# COPY_VestibularVR_H1-module_v1_0.net
KiCad netlist of a schematic drawn in EAGLE
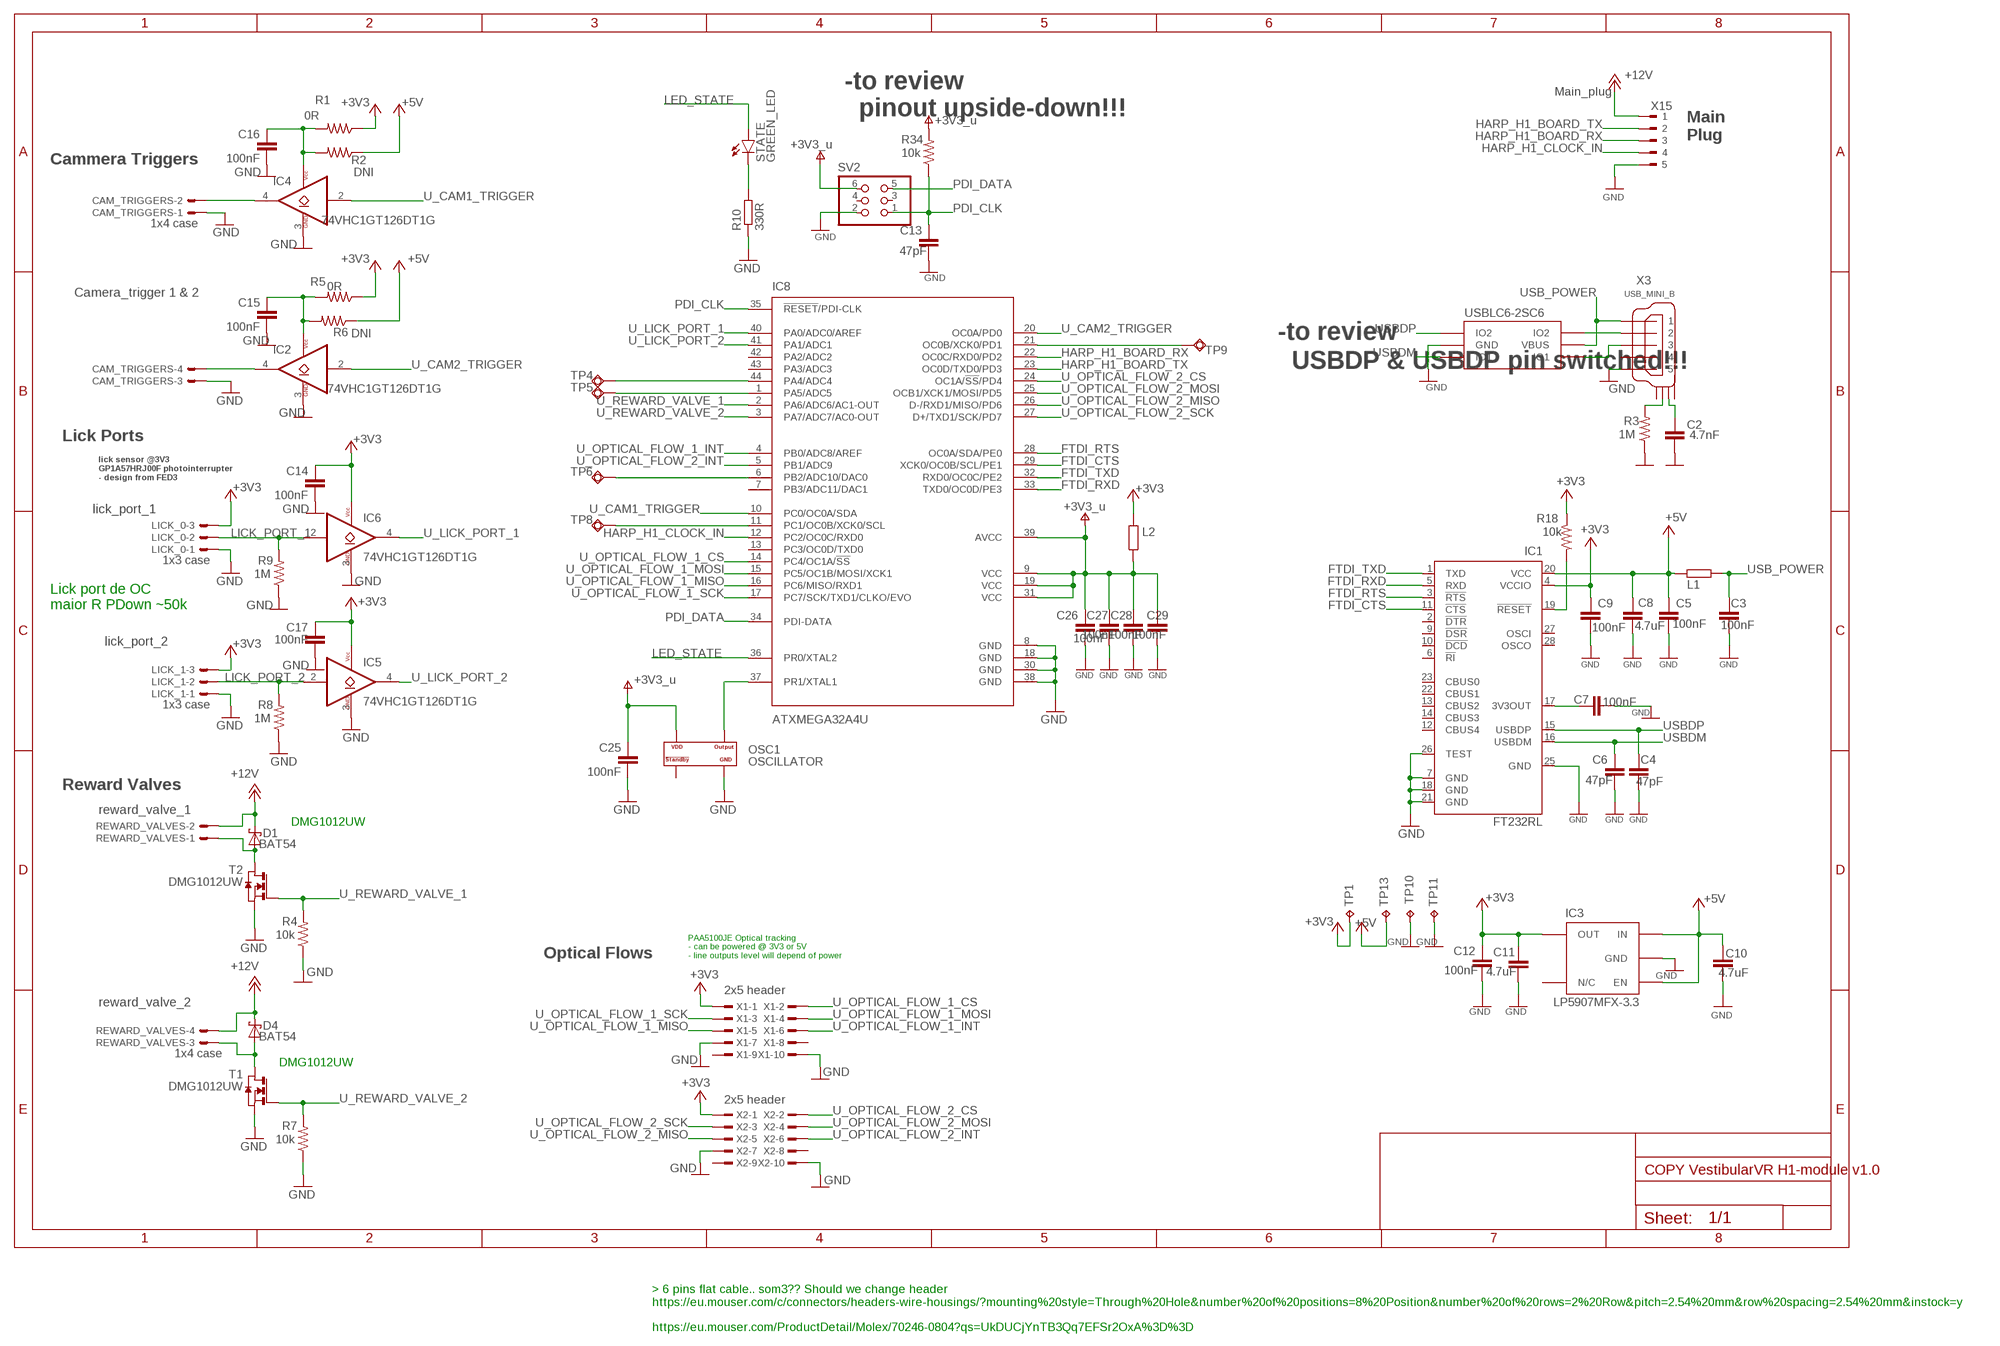
[diagram p0: schematic, sheet 1]

(export (version "E")
  (design (tool "Eeschema 10.0.6"))
  (components
    (comp (ref "C2")
      (value "4.7nF")
      (footprint "eagle-import:C0402K")
      (fields (field (name "MPN") "CC0402KRX7R8BB472"))
      (libsource (lib "eagle-import") (part "C-EUC0402K"))
    )
    (comp (ref "C3")
      (value "100nF")
      (footprint "eagle-import:C0402K")
      (fields (field (name "MPN") "C1005X7R1H104K050BB"))
      (libsource (lib "eagle-import") (part "C-EUC0402K"))
    )
    (comp (ref "C4")
      (value "47pF")
      (footprint "eagle-import:C0402K")
      (fields (field (name "MPN") "04025A470JAT2A"))
      (libsource (lib "eagle-import") (part "C-EUC0402K"))
    )
    (comp (ref "C5")
      (value "100nF")
      (footprint "eagle-import:C0402K")
      (fields (field (name "MPN") "C1005X7R1H104K050BB"))
      (libsource (lib "eagle-import") (part "C-EUC0402K"))
    )
    (comp (ref "C6")
      (value "47pF")
      (footprint "eagle-import:C0402K")
      (fields (field (name "MPN") "04025A470JAT2A"))
      (libsource (lib "eagle-import") (part "C-EUC0402K"))
    )
    (comp (ref "C7")
      (value "100nF")
      (footprint "eagle-import:C0402K")
      (fields (field (name "MPN") "C1005X7R1H104K050BB"))
      (libsource (lib "eagle-import") (part "C-EUC0402K"))
    )
    (comp (ref "C8")
      (value "4.7uF")
      (footprint "eagle-import:C0603")
      (fields (field (name "MPN") "C1608X6S1C475K080AC"))
      (libsource (lib "eagle-import") (part "C-EUC0603"))
    )
    (comp (ref "C9")
      (value "100nF")
      (footprint "eagle-import:C0402K")
      (fields (field (name "MPN") "C1005X7R1H104K050BB"))
      (libsource (lib "eagle-import") (part "C-EUC0402K"))
    )
    (comp (ref "C10")
      (value "4.7uF")
      (footprint "eagle-import:C0603K")
      (fields (field (name "MPN") "C1608X6S1C475K080AC"))
      (libsource (lib "eagle-import") (part "C-EUC0603K"))
    )
    (comp (ref "C11")
      (value "4.7uF")
      (footprint "eagle-import:C0603K")
      (fields (field (name "MPN") "C1608X6S1C475K080AC"))
      (libsource (lib "eagle-import") (part "C-EUC0603K"))
    )
    (comp (ref "C12")
      (value "100nF")
      (footprint "eagle-import:C0402K")
      (fields (field (name "MPN") "C1005X7R1H104K050BB"))
      (libsource (lib "eagle-import") (part "C-EUC0402K"))
    )
    (comp (ref "C13")
      (value "47pF")
      (footprint "eagle-import:C0402K")
      (fields (field (name "MPN") "04025A470JAT2A"))
      (libsource (lib "eagle-import") (part "C-EUC0402K"))
    )
    (comp (ref "C14")
      (value "100nF")
      (footprint "eagle-import:C0402K")
      (fields (field (name "MPN") "C1005X7R1H104K050BB"))
      (libsource (lib "eagle-import") (part "C-EUC0402K"))
    )
    (comp (ref "C15")
      (value "100nF")
      (footprint "eagle-import:C0402K")
      (fields (field (name "MPN") "C1005X7R1H104K050BB"))
      (libsource (lib "eagle-import") (part "C-EUC0402K"))
    )
    (comp (ref "C16")
      (value "100nF")
      (footprint "eagle-import:C0402K")
      (fields (field (name "MPN") "C1005X7R1H104K050BB"))
      (libsource (lib "eagle-import") (part "C-EUC0402K"))
    )
    (comp (ref "C17")
      (value "100nF")
      (footprint "eagle-import:C0402K")
      (fields (field (name "MPN") "C1005X7R1H104K050BB"))
      (libsource (lib "eagle-import") (part "C-EUC0402K"))
    )
    (comp (ref "C25")
      (value "100nF")
      (footprint "eagle-import:C0402K")
      (fields (field (name "MPN") "C1005X7R1H104K050BB"))
      (libsource (lib "eagle-import") (part "C-EUC0402K"))
    )
    (comp (ref "C26")
      (value "100nF")
      (footprint "eagle-import:C0402K")
      (fields (field (name "MPN") "C1005X7R1H104K050BB"))
      (libsource (lib "eagle-import") (part "C-EUC0402K"))
    )
    (comp (ref "C27")
      (value "100nF")
      (footprint "eagle-import:C0402K")
      (fields (field (name "MPN") "C1005X7R1H104K050BB"))
      (libsource (lib "eagle-import") (part "C-EUC0402K"))
    )
    (comp (ref "C28")
      (value "100nF")
      (footprint "eagle-import:C0402K")
      (fields (field (name "MPN") "C1005X7R1H104K050BB"))
      (libsource (lib "eagle-import") (part "C-EUC0402K"))
    )
    (comp (ref "C29")
      (value "100nF")
      (footprint "eagle-import:C0402K")
      (fields (field (name "MPN") "C1005X7R1H104K050BB"))
      (libsource (lib "eagle-import") (part "C-EUC0402K"))
    )
    (comp (ref "CAM_TRIGGERS")
      (value "1x4 case")
      (footprint "eagle-import:22-23-2041")
      (fields
        (field (name "MF") "MOLEX")
        (field (name "MPN") "22-23-2041")
        (field (name "MF_1") "-")
        (field (name "MPN_1") "282834-4")
        (field (name "OEPS") "OEPS070036")
      )
      (libsource (lib "eagle-import") (part "22-23-2041"))
    )
    (comp (ref "D1")
      (value "BAT54")
      (footprint "eagle-import:SOT23")
      (fields (field (name "MPN") "BAT54SLT1G"))
      (libsource (lib "eagle-import") (part "BAT54"))
    )
    (comp (ref "D4")
      (value "BAT54")
      (footprint "eagle-import:SOT23")
      (fields (field (name "MPN") "BAT54SLT1G"))
      (libsource (lib "eagle-import") (part "BAT54"))
    )
    (comp (ref "IC1")
      (value "FT232RL")
      (footprint "eagle-import:SSOP28")
      (libsource (lib "eagle-import") (part "FT232RL"))
    )
    (comp (ref "IC2")
      (value "74VHC1GT126DT1G")
      (footprint "eagle-import:SOT23-5")
      (fields (field (name "MPN") "M74VHC1GT126DT1G"))
      (libsource (lib "eagle-import") (part "74LVC1G07DBV"))
    )
    (comp (ref "IC3")
      (value "LP5907MFX-3.3")
      (footprint "eagle-import:TSOT23-5")
      (fields (field (name "MPN") "LP5907MFX-3.3/NOPB"))
      (libsource (lib "eagle-import") (part "TLV700XX"))
    )
    (comp (ref "IC4")
      (value "74VHC1GT126DT1G")
      (footprint "eagle-import:SOT23-5")
      (fields (field (name "MPN") "M74VHC1GT126DT1G"))
      (libsource (lib "eagle-import") (part "74LVC1G07DBV"))
    )
    (comp (ref "IC5")
      (value "74VHC1GT126DT1G")
      (footprint "eagle-import:SOT23-5")
      (fields (field (name "MPN") "M74VHC1GT126DT1G"))
      (libsource (lib "eagle-import") (part "74LVC1G07DBV"))
    )
    (comp (ref "IC6")
      (value "74VHC1GT126DT1G")
      (footprint "eagle-import:SOT23-5")
      (fields (field (name "MPN") "M74VHC1GT126DT1G"))
      (libsource (lib "eagle-import") (part "74LVC1G07DBV"))
    )
    (comp (ref "IC7")
      (value "USBLC6-2SC6")
      (footprint "eagle-import:SOT23-6L")
      (libsource (lib "eagle-import") (part "USBLC6-2SC6"))
    )
    (comp (ref "IC8")
      (value "ATXMEGA32A4U")
      (footprint "eagle-import:TQFP44")
      (fields (field (name "MPN") "ATXMEGA32A4U-AUR"))
      (libsource (lib "eagle-import") (part "XMEGA-A4_AT-XMEGA-XXA4-AUTQFP44"))
    )
    (comp (ref "L1")
      (value "40R@100MHz")
      (footprint "eagle-import:R0603")
      (fields (field (name "MPN") "MI0805K400R-10"))
      (libsource (lib "eagle-import") (part "R-EU_R0603"))
    )
    (comp (ref "L2")
      (value "40R@100MHz")
      (footprint "eagle-import:R0603")
      (fields (field (name "MPN") "MI0805K400R-10"))
      (libsource (lib "eagle-import") (part "R-EU_R0603"))
    )
    (comp (ref "LICK_0")
      (value "1x3 case")
      (footprint "eagle-import:22-23-2031")
      (fields
        (field (name "MF") "MOLEX")
        (field (name "MPN") "22-23-2031")
        (field (name "MF_1") "-")
        (field (name "MPN_1") "282834-3")
        (field (name "OEPS") "OEPS070035")
      )
      (libsource (lib "eagle-import") (part "22-23-2031"))
    )
    (comp (ref "LICK_1")
      (value "1x3 case")
      (footprint "eagle-import:22-23-2031")
      (fields
        (field (name "MF") "MOLEX")
        (field (name "MPN") "22-23-2031")
        (field (name "MF_1") "-")
        (field (name "MPN_1") "282834-3")
        (field (name "OEPS") "OEPS070035")
      )
      (libsource (lib "eagle-import") (part "22-23-2031"))
    )
    (comp (ref "OSC1")
      (value "OSCILLATOR")
      (footprint "eagle-import:OSCILLATOR_3.2X2.5")
      (fields (field (name "MPN") "DSC1001CI5-032.0000"))
      (libsource (lib "eagle-import") (part "OSCILLATOR"))
    )
    (comp (ref "R1")
      (value "0R")
      (footprint "eagle-import:R0402@1")
      (fields (field (name "MPN") "RC0402JR-070RL"))
      (libsource (lib "eagle-import") (part "R-US_R0402"))
    )
    (comp (ref "R2")
      (value "DNI")
      (footprint "eagle-import:R0402@1")
      (libsource (lib "eagle-import") (part "R-US_R0402"))
    )
    (comp (ref "R3")
      (value "1M")
      (footprint "eagle-import:R0402@1")
      (fields (field (name "MPN") "CRCW04021M00FKED"))
      (libsource (lib "eagle-import") (part "R-US_R0402"))
    )
    (comp (ref "R4")
      (value "10k")
      (footprint "eagle-import:R0402@1")
      (fields (field (name "MPN") "CRCW040210K0FKED"))
      (libsource (lib "eagle-import") (part "R-US_R0402"))
    )
    (comp (ref "R5")
      (value "0R")
      (footprint "eagle-import:R0402@1")
      (fields (field (name "MPN") "RC0402JR-070RL"))
      (libsource (lib "eagle-import") (part "R-US_R0402"))
    )
    (comp (ref "R6")
      (value "DNI")
      (footprint "eagle-import:R0402@1")
      (libsource (lib "eagle-import") (part "R-US_R0402"))
    )
    (comp (ref "R7")
      (value "10k")
      (footprint "eagle-import:R0402@1")
      (fields (field (name "MPN") "CRCW040210K0FKED"))
      (libsource (lib "eagle-import") (part "R-US_R0402"))
    )
    (comp (ref "R8")
      (value "1M")
      (footprint "eagle-import:R0402@1")
      (fields (field (name "MPN") "CRCW04021M00FKED"))
      (libsource (lib "eagle-import") (part "R-US_R0402"))
    )
    (comp (ref "R9")
      (value "1M")
      (footprint "eagle-import:R0402@1")
      (fields (field (name "MPN") "CRCW04021M00FKED"))
      (libsource (lib "eagle-import") (part "R-US_R0402"))
    )
    (comp (ref "R10")
      (value "330R")
      (footprint "eagle-import:R0402")
      (fields (field (name "MPN") "RC0402FR-07330RL"))
      (libsource (lib "eagle-import") (part "R-EU_R0402"))
    )
    (comp (ref "R18")
      (value "10k")
      (footprint "eagle-import:R0402@1")
      (fields (field (name "MPN") "CRCW040210K0FKED"))
      (libsource (lib "eagle-import") (part "R-US_R0402"))
    )
    (comp (ref "R34")
      (value "10k")
      (footprint "eagle-import:R0402@1")
      (fields (field (name "MPN") "CRCW040210K0FKED"))
      (libsource (lib "eagle-import") (part "R-US_R0402"))
    )
    (comp (ref "REWARD_VALVES")
      (value "1x4 case")
      (footprint "eagle-import:22-23-2041")
      (fields
        (field (name "MF") "MOLEX")
        (field (name "MPN") "22-23-2041")
        (field (name "MF_1") "-")
        (field (name "MPN_1") "282834-4")
        (field (name "OEPS") "OEPS070036")
      )
      (libsource (lib "eagle-import") (part "22-23-2041"))
    )
    (comp (ref "STATE")
      (value "GREEN_LED")
      (footprint "eagle-import:CHIP-LED0603")
      (fields (field (name "MPN") "LTST-C191KGKT"))
      (libsource (lib "eagle-import") (part "LEDCHIP-LED0603"))
    )
    (comp (ref "SV2")
      (value "PINHD-2X3")
      (footprint "eagle-import:2X03")
      (fields (field (name "MPN") "609-3210-ND"))
      (libsource (lib "eagle-import") (part "PINHD-2X3"))
    )
    (comp (ref "T1")
      (value "DMG1012UW")
      (footprint "eagle-import:SOT323")
      (fields (field (name "MPN") "DMG1012UW-7"))
      (libsource (lib "eagle-import") (part "DMG1012UW-7"))
    )
    (comp (ref "T2")
      (value "DMG1012UW")
      (footprint "eagle-import:SOT323")
      (fields (field (name "MPN") "DMG1012UW-7"))
      (libsource (lib "eagle-import") (part "DMG1012UW-7"))
    )
    (comp (ref "TP1")
      (value "NO_COMPONENT")
      (footprint "eagle-import:B1,27")
      (libsource (lib "eagle-import") (part "TPB1,27"))
    )
    (comp (ref "TP4")
      (value "NO_COMPONENT")
      (footprint "eagle-import:TP11R")
      (libsource (lib "eagle-import") (part "TPSQTP11R"))
    )
    (comp (ref "TP5")
      (value "NO_COMPONENT")
      (footprint "eagle-import:TP11R")
      (libsource (lib "eagle-import") (part "TPSQTP11R"))
    )
    (comp (ref "TP6")
      (value "NO_COMPONENT")
      (footprint "eagle-import:TP11R")
      (libsource (lib "eagle-import") (part "TPSQTP11R"))
    )
    (comp (ref "TP8")
      (value "NO_COMPONENT")
      (footprint "eagle-import:TP11R")
      (libsource (lib "eagle-import") (part "TPSQTP11R"))
    )
    (comp (ref "TP9")
      (value "NO_COMPONENT")
      (footprint "eagle-import:TP11R")
      (libsource (lib "eagle-import") (part "TPSQTP11R"))
    )
    (comp (ref "TP10")
      (value "NO_COMPONENT")
      (footprint "eagle-import:B1,27")
      (libsource (lib "eagle-import") (part "TPB1,27"))
    )
    (comp (ref "TP11")
      (value "NO_COMPONENT")
      (footprint "eagle-import:B1,27")
      (libsource (lib "eagle-import") (part "TPB1,27"))
    )
    (comp (ref "TP13")
      (value "NO_COMPONENT")
      (footprint "eagle-import:B1,27")
      (libsource (lib "eagle-import") (part "TPB1,27"))
    )
    (comp (ref "X1")
      (value "2x5 header")
      (footprint "eagle-import:TSW-105-02-S-D")
      (fields (field (name "MPN") "2x5 header") (field (name "OEPS") "n.a."))
      (libsource (lib "eagle-import") (part "TSW-105-02-S-D"))
    )
    (comp (ref "X2")
      (value "2x5 header")
      (footprint "eagle-import:TSW-105-02-S-D")
      (fields (field (name "MPN") "2x5 header") (field (name "OEPS") "n.a."))
      (libsource (lib "eagle-import") (part "TSW-105-02-S-D"))
    )
    (comp (ref "X3")
      (value "USB_MINI_B")
      (footprint "eagle-import:240-0002-1")
      (fields (field (name "MPN") "UX60-MB-5S8"))
      (libsource (lib "eagle-import") (part "USB_MINI_B"))
    )
    (comp (ref "X15")
      (value "Main_plug")
      (footprint "eagle-import:90G-5")
      (fields (field (name "MPN") "20.155MH/5-E"))
      (libsource (lib "eagle-import") (part "90G-5"))
    )
  )
  (nets
    (net (code "1") (name "+3V3") (class "Default")
      (node (ref "C11") (pin "1") (pinfunction "1_1") (pintype "passive"))
      (node (ref "C12") (pin "1") (pinfunction "1_1") (pintype "passive"))
      (node (ref "C14") (pin "1") (pinfunction "1_1") (pintype "passive"))
      (node (ref "C17") (pin "1") (pinfunction "1_1") (pintype "passive"))
      (node (ref "C9") (pin "1") (pinfunction "1_1") (pintype "passive"))
      (node (ref "IC1") (pin "4") (pinfunction "VCCIO_4") (pintype "power_in"))
      (node (ref "IC3") (pin "5") (pinfunction "OUT_5") (pintype "bidirectional"))
      (node (ref "IC5") (pin "5") (pinfunction "VCC_5") (pintype "bidirectional"))
      (node (ref "IC6") (pin "5") (pinfunction "VCC_5") (pintype "bidirectional"))
      (node (ref "L2") (pin "2") (pinfunction "2_2") (pintype "passive"))
      (node (ref "LICK_0") (pin "3") (pinfunction "S_3") (pintype "passive"))
      (node (ref "LICK_1") (pin "3") (pinfunction "S_3") (pintype "passive"))
      (node (ref "R1") (pin "1") (pinfunction "1_1") (pintype "passive"))
      (node (ref "R18") (pin "1") (pinfunction "1_1") (pintype "passive"))
      (node (ref "R5") (pin "1") (pinfunction "1_1") (pintype "passive"))
      (node (ref "TP1") (pin "TP") (pinfunction "TP_TP") (pintype "input"))
      (node (ref "X1") (pin "1") (pinfunction "1_1") (pintype "passive"))
      (node (ref "X2") (pin "1") (pinfunction "1_1") (pintype "passive"))
    )
    (net (code "2") (name "+3V3_u") (class "Default")
      (node (ref "C25") (pin "1") (pinfunction "1_1") (pintype "passive"))
      (node (ref "C26") (pin "1") (pinfunction "1_1") (pintype "passive"))
      (node (ref "C27") (pin "1") (pinfunction "1_1") (pintype "passive"))
      (node (ref "C28") (pin "1") (pinfunction "1_1") (pintype "passive"))
      (node (ref "C29") (pin "1") (pinfunction "1_1") (pintype "passive"))
      (node (ref "IC8") (pin "19") (pinfunction "VCC_19") (pintype "power_in"))
      (node (ref "IC8") (pin "31") (pinfunction "VCC_31") (pintype "power_in"))
      (node (ref "IC8") (pin "39") (pinfunction "AVCC_39") (pintype "power_in"))
      (node (ref "IC8") (pin "9") (pinfunction "VCC_9") (pintype "power_in"))
      (node (ref "L2") (pin "1") (pinfunction "1_1") (pintype "passive"))
      (node (ref "OSC1") (pin "P$4") (pinfunction "VDD_P$4") (pintype "passive"))
      (node (ref "R34") (pin "2") (pinfunction "2_2") (pintype "passive"))
      (node (ref "SV2") (pin "6") (pinfunction "6_6") (pintype "passive"))
    )
    (net (code "3") (name "+5V") (class "Default")
      (node (ref "C10") (pin "1") (pinfunction "1_1") (pintype "passive"))
      (node (ref "C5") (pin "1") (pinfunction "1_1") (pintype "passive"))
      (node (ref "C8") (pin "1") (pinfunction "1_1") (pintype "passive"))
      (node (ref "IC1") (pin "20") (pinfunction "VCC_20") (pintype "power_in"))
      (node (ref "IC3") (pin "1") (pinfunction "IN_1") (pintype "bidirectional"))
      (node (ref "IC3") (pin "3") (pinfunction "EN_3") (pintype "bidirectional"))
      (node (ref "L1") (pin "1") (pinfunction "1_1") (pintype "passive"))
      (node (ref "R2") (pin "1") (pinfunction "1_1") (pintype "passive"))
      (node (ref "R6") (pin "1") (pinfunction "1_1") (pintype "passive"))
      (node (ref "TP13") (pin "TP") (pinfunction "TP_TP") (pintype "input"))
    )
    (net (code "4") (name "+12V") (class "Default")
      (node (ref "D1") (pin "3") (pinfunction "C_3") (pintype "passive"))
      (node (ref "D4") (pin "3") (pinfunction "C_3") (pintype "passive"))
      (node (ref "REWARD_VALVES") (pin "2") (pinfunction "S_2") (pintype "passive"))
      (node (ref "REWARD_VALVES") (pin "4") (pinfunction "S_4") (pintype "passive"))
      (node (ref "X15") (pin "1") (pinfunction "1_1") (pintype "passive"))
    )
    (net (code "5") (name "/FTDI_CTS") (class "Default")
      (node (ref "IC1") (pin "11") (pinfunction "~{CTS}_11") (pintype "input"))
      (node (ref "IC8") (pin "29") (pinfunction "XCK0/OC0B/SCL/PE1_29") (pintype "bidirectional"))
    )
    (net (code "6") (name "/FTDI_RTS") (class "Default")
      (node (ref "IC1") (pin "3") (pinfunction "~{RTS}_3") (pintype "output"))
      (node (ref "IC8") (pin "28") (pinfunction "OC0A/SDA/PE0_28") (pintype "bidirectional"))
    )
    (net (code "7") (name "/FTDI_RXD") (class "Default")
      (node (ref "IC1") (pin "5") (pinfunction "RXD_5") (pintype "input"))
      (node (ref "IC8") (pin "33") (pinfunction "TXD0/OC0D/PE3_33") (pintype "bidirectional"))
    )
    (net (code "8") (name "/FTDI_TXD") (class "Default")
      (node (ref "IC1") (pin "1") (pinfunction "TXD_1") (pintype "output"))
      (node (ref "IC8") (pin "32") (pinfunction "RXD0/OC0C/PE2_32") (pintype "bidirectional"))
    )
    (net (code "9") (name "/HARP_H1_BOARD_RX") (class "Default")
      (node (ref "IC8") (pin "22") (pinfunction "OC0C/RXD0/PD2_22") (pintype "bidirectional"))
      (node (ref "X15") (pin "3") (pinfunction "3_3") (pintype "passive"))
    )
    (net (code "10") (name "/HARP_H1_BOARD_TX") (class "Default")
      (node (ref "IC8") (pin "23") (pinfunction "OC0D/TXD0/PD3_23") (pintype "bidirectional"))
      (node (ref "X15") (pin "2") (pinfunction "2_2") (pintype "passive"))
    )
    (net (code "11") (name "/HARP_H1_CLOCK_IN") (class "Default")
      (node (ref "IC8") (pin "12") (pinfunction "PC2/OC0C/RXD0_12") (pintype "bidirectional"))
      (node (ref "X15") (pin "4") (pinfunction "4_4") (pintype "passive"))
    )
    (net (code "12") (name "/LED_STATE") (class "Default")
      (node (ref "IC8") (pin "36") (pinfunction "PR0/XTAL2_36") (pintype "bidirectional"))
      (node (ref "STATE") (pin "A") (pinfunction "A_A") (pintype "passive"))
    )
    (net (code "13") (name "/LICK_PORT_1") (class "Default")
      (node (ref "IC6") (pin "2") (pinfunction "A_2") (pintype "bidirectional"))
      (node (ref "LICK_0") (pin "2") (pinfunction "S_2") (pintype "passive"))
      (node (ref "R9") (pin "2") (pinfunction "2_2") (pintype "passive"))
    )
    (net (code "14") (name "/LICK_PORT_2") (class "Default")
      (node (ref "IC5") (pin "2") (pinfunction "A_2") (pintype "bidirectional"))
      (node (ref "LICK_1") (pin "2") (pinfunction "S_2") (pintype "passive"))
      (node (ref "R8") (pin "2") (pinfunction "2_2") (pintype "passive"))
    )
    (net (code "15") (name "/PDI_CLK") (class "Default")
      (node (ref "C13") (pin "1") (pinfunction "1_1") (pintype "passive"))
      (node (ref "IC8") (pin "35") (pinfunction "~{RESET}/PDI-CLK_35") (pintype "input"))
      (node (ref "R34") (pin "1") (pinfunction "1_1") (pintype "passive"))
      (node (ref "SV2") (pin "1") (pinfunction "1_1") (pintype "passive"))
    )
    (net (code "16") (name "/PDI_DATA") (class "Default")
      (node (ref "IC8") (pin "34") (pinfunction "PDI-DATA_34") (pintype "bidirectional"))
      (node (ref "SV2") (pin "5") (pinfunction "5_5") (pintype "passive"))
    )
    (net (code "17") (name "/USBDM") (class "Default")
      (node (ref "C6") (pin "1") (pinfunction "1_1") (pintype "passive"))
      (node (ref "IC1") (pin "16") (pinfunction "USBDM_16") (pintype "bidirectional"))
      (node (ref "IC7") (pin "P$1") (pinfunction "IO1_P$1") (pintype "bidirectional"))
    )
    (net (code "18") (name "/USBDP") (class "Default")
      (node (ref "C4") (pin "1") (pinfunction "1_1") (pintype "passive"))
      (node (ref "IC1") (pin "15") (pinfunction "USBDP_15") (pintype "bidirectional"))
      (node (ref "IC7") (pin "P$3") (pinfunction "IO2_P$3") (pintype "bidirectional"))
    )
    (net (code "19") (name "/USB_POWER") (class "Default")
      (node (ref "C3") (pin "1") (pinfunction "1_1") (pintype "passive"))
      (node (ref "IC7") (pin "P$5") (pinfunction "VBUS_P$5") (pintype "bidirectional"))
      (node (ref "L1") (pin "2") (pinfunction "2_2") (pintype "passive"))
      (node (ref "X3") (pin "P$1") (pinfunction "1_P$1") (pintype "bidirectional"))
    )
    (net (code "20") (name "/U_CAM1_TRIGGER") (class "Default")
      (node (ref "IC4") (pin "2") (pinfunction "A_2") (pintype "bidirectional"))
      (node (ref "IC8") (pin "10") (pinfunction "PC0/OC0A/SDA_10") (pintype "bidirectional"))
    )
    (net (code "21") (name "/U_CAM2_TRIGGER") (class "Default")
      (node (ref "IC2") (pin "2") (pinfunction "A_2") (pintype "bidirectional"))
      (node (ref "IC8") (pin "20") (pinfunction "OC0A/PD0_20") (pintype "bidirectional"))
    )
    (net (code "22") (name "/U_LICK_PORT_1") (class "Default")
      (node (ref "IC6") (pin "4") (pinfunction "Y_4") (pintype "bidirectional"))
      (node (ref "IC8") (pin "40") (pinfunction "PA0/ADC0/AREF_40") (pintype "bidirectional"))
    )
    (net (code "23") (name "/U_LICK_PORT_2") (class "Default")
      (node (ref "IC5") (pin "4") (pinfunction "Y_4") (pintype "bidirectional"))
      (node (ref "IC8") (pin "41") (pinfunction "PA1/ADC1_41") (pintype "bidirectional"))
    )
    (net (code "24") (name "/U_OPTICAL_FLOW_1_CS") (class "Default")
      (node (ref "IC8") (pin "14") (pinfunction "PC4/OC1A/~{SS}_14") (pintype "bidirectional"))
      (node (ref "X1") (pin "2") (pinfunction "1_2") (pintype "passive"))
    )
    (net (code "25") (name "/U_OPTICAL_FLOW_1_INT") (class "Default")
      (node (ref "IC8") (pin "4") (pinfunction "PB0/ADC8/AREF_4") (pintype "bidirectional"))
      (node (ref "X1") (pin "6") (pinfunction "1_6") (pintype "passive"))
    )
    (net (code "26") (name "/U_OPTICAL_FLOW_1_MISO") (class "Default")
      (node (ref "IC8") (pin "16") (pinfunction "PC6/MISO/RXD1_16") (pintype "bidirectional"))
      (node (ref "X1") (pin "5") (pinfunction "1_5") (pintype "passive"))
    )
    (net (code "27") (name "/U_OPTICAL_FLOW_1_MOSI") (class "Default")
      (node (ref "IC8") (pin "15") (pinfunction "PC5/OC1B/MOSI/XCK1_15") (pintype "bidirectional"))
      (node (ref "X1") (pin "4") (pinfunction "1_4") (pintype "passive"))
    )
    (net (code "28") (name "/U_OPTICAL_FLOW_1_SCK") (class "Default")
      (node (ref "IC8") (pin "17") (pinfunction "PC7/SCK/TXD1/CLKO/EVO_17") (pintype "bidirectional"))
      (node (ref "X1") (pin "3") (pinfunction "1_3") (pintype "passive"))
    )
    (net (code "29") (name "/U_OPTICAL_FLOW_2_CS") (class "Default")
      (node (ref "IC8") (pin "24") (pinfunction "OC1A/~{SS}/PD4_24") (pintype "bidirectional"))
      (node (ref "X2") (pin "2") (pinfunction "1_2") (pintype "passive"))
    )
    (net (code "30") (name "/U_OPTICAL_FLOW_2_INT") (class "Default")
      (node (ref "IC8") (pin "5") (pinfunction "PB1/ADC9_5") (pintype "bidirectional"))
      (node (ref "X2") (pin "6") (pinfunction "1_6") (pintype "passive"))
    )
    (net (code "31") (name "/U_OPTICAL_FLOW_2_MISO") (class "Default")
      (node (ref "IC8") (pin "26") (pinfunction "D-/RXD1/MISO/PD6_26") (pintype "bidirectional"))
      (node (ref "X2") (pin "5") (pinfunction "1_5") (pintype "passive"))
    )
    (net (code "32") (name "/U_OPTICAL_FLOW_2_MOSI") (class "Default")
      (node (ref "IC8") (pin "25") (pinfunction "OCB1/XCK1/MOSI/PD5_25") (pintype "bidirectional"))
      (node (ref "X2") (pin "4") (pinfunction "1_4") (pintype "passive"))
    )
    (net (code "33") (name "/U_OPTICAL_FLOW_2_SCK") (class "Default")
      (node (ref "IC8") (pin "27") (pinfunction "D+/TXD1/SCK/PD7_27") (pintype "bidirectional"))
      (node (ref "X2") (pin "3") (pinfunction "1_3") (pintype "passive"))
    )
    (net (code "34") (name "/U_REWARD_VALVE_1") (class "Default")
      (node (ref "IC8") (pin "2") (pinfunction "PA6/ADC6/AC1-OUT_2") (pintype "bidirectional"))
      (node (ref "R4") (pin "2") (pinfunction "2_2") (pintype "passive"))
      (node (ref "T2") (pin "1") (pinfunction "G_1") (pintype "passive"))
    )
    (net (code "35") (name "/U_REWARD_VALVE_2") (class "Default")
      (node (ref "IC8") (pin "3") (pinfunction "PA7/ADC7/AC0-OUT_3") (pintype "bidirectional"))
      (node (ref "R7") (pin "2") (pinfunction "2_2") (pintype "passive"))
      (node (ref "T1") (pin "1") (pinfunction "G_1") (pintype "passive"))
    )
    (net (code "36") (name "GND") (class "Default")
      (node (ref "C10") (pin "2") (pinfunction "2_2") (pintype "passive"))
      (node (ref "C11") (pin "2") (pinfunction "2_2") (pintype "passive"))
      (node (ref "C12") (pin "2") (pinfunction "2_2") (pintype "passive"))
      (node (ref "C13") (pin "2") (pinfunction "2_2") (pintype "passive"))
      (node (ref "C14") (pin "2") (pinfunction "2_2") (pintype "passive"))
      (node (ref "C15") (pin "2") (pinfunction "2_2") (pintype "passive"))
      (node (ref "C16") (pin "2") (pinfunction "2_2") (pintype "passive"))
      (node (ref "C17") (pin "2") (pinfunction "2_2") (pintype "passive"))
      (node (ref "C2") (pin "2") (pinfunction "2_2") (pintype "passive"))
      (node (ref "C25") (pin "2") (pinfunction "2_2") (pintype "passive"))
      (node (ref "C26") (pin "2") (pinfunction "2_2") (pintype "passive"))
      (node (ref "C27") (pin "2") (pinfunction "2_2") (pintype "passive"))
      (node (ref "C28") (pin "2") (pinfunction "2_2") (pintype "passive"))
      (node (ref "C29") (pin "2") (pinfunction "2_2") (pintype "passive"))
      (node (ref "C3") (pin "2") (pinfunction "2_2") (pintype "passive"))
      (node (ref "C4") (pin "2") (pinfunction "2_2") (pintype "passive"))
      (node (ref "C5") (pin "2") (pinfunction "2_2") (pintype "passive"))
      (node (ref "C6") (pin "2") (pinfunction "2_2") (pintype "passive"))
      (node (ref "C7") (pin "2") (pinfunction "2_2") (pintype "passive"))
      (node (ref "C8") (pin "2") (pinfunction "2_2") (pintype "passive"))
      (node (ref "C9") (pin "2") (pinfunction "2_2") (pintype "passive"))
      (node (ref "CAM_TRIGGERS") (pin "1") (pinfunction "S_1") (pintype "passive"))
      (node (ref "CAM_TRIGGERS") (pin "3") (pinfunction "S_3") (pintype "passive"))
      (node (ref "IC1") (pin "18") (pinfunction "GND_18") (pintype "power_in"))
      (node (ref "IC1") (pin "21") (pinfunction "GND_21") (pintype "power_in"))
      (node (ref "IC1") (pin "25") (pinfunction "GND_25") (pintype "power_in"))
      (node (ref "IC1") (pin "26") (pinfunction "TEST_26") (pintype "input"))
      (node (ref "IC1") (pin "7") (pinfunction "GND_7") (pintype "power_in"))
      (node (ref "IC2") (pin "3") (pinfunction "GND_3") (pintype "bidirectional"))
      (node (ref "IC3") (pin "2") (pinfunction "GND_2") (pintype "bidirectional"))
      (node (ref "IC4") (pin "3") (pinfunction "GND_3") (pintype "bidirectional"))
      (node (ref "IC5") (pin "3") (pinfunction "GND_3") (pintype "bidirectional"))
      (node (ref "IC6") (pin "3") (pinfunction "GND_3") (pintype "bidirectional"))
      (node (ref "IC7") (pin "P$2") (pinfunction "GND_P$2") (pintype "bidirectional"))
      (node (ref "IC8") (pin "18") (pinfunction "GND_18") (pintype "power_in"))
      (node (ref "IC8") (pin "30") (pinfunction "GND_30") (pintype "power_in"))
      (node (ref "IC8") (pin "38") (pinfunction "GND_38") (pintype "power_in"))
      (node (ref "IC8") (pin "8") (pinfunction "GND_8") (pintype "power_in"))
      (node (ref "LICK_0") (pin "1") (pinfunction "S_1") (pintype "passive"))
      (node (ref "LICK_1") (pin "1") (pinfunction "S_1") (pintype "passive"))
      (node (ref "OSC1") (pin "P$2") (pinfunction "GND_P$2") (pintype "passive"))
      (node (ref "R10") (pin "1") (pinfunction "1_1") (pintype "passive"))
      (node (ref "R3") (pin "1") (pinfunction "1_1") (pintype "passive"))
      (node (ref "R4") (pin "1") (pinfunction "1_1") (pintype "passive"))
      (node (ref "R7") (pin "1") (pinfunction "1_1") (pintype "passive"))
      (node (ref "R8") (pin "1") (pinfunction "1_1") (pintype "passive"))
      (node (ref "R9") (pin "1") (pinfunction "1_1") (pintype "passive"))
      (node (ref "SV2") (pin "2") (pinfunction "2_2") (pintype "passive"))
      (node (ref "T1") (pin "2") (pinfunction "S_2") (pintype "passive"))
      (node (ref "T2") (pin "2") (pinfunction "S_2") (pintype "passive"))
      (node (ref "TP10") (pin "TP") (pinfunction "TP_TP") (pintype "input"))
      (node (ref "TP11") (pin "TP") (pinfunction "TP_TP") (pintype "input"))
      (node (ref "X1") (pin "10") (pinfunction "1_10") (pintype "passive"))
      (node (ref "X1") (pin "7") (pinfunction "1_7") (pintype "passive"))
      (node (ref "X15") (pin "5") (pinfunction "5_5") (pintype "passive"))
      (node (ref "X2") (pin "10") (pinfunction "1_10") (pintype "passive"))
      (node (ref "X2") (pin "7") (pinfunction "1_7") (pintype "passive"))
      (node (ref "X3") (pin "P$5") (pinfunction "5_P$5") (pintype "bidirectional"))
    )
    (net (code "37") (name "Net-(CAM_TRIGGERSB-S)") (class "Default")
      (node (ref "CAM_TRIGGERS") (pin "2") (pinfunction "S_2") (pintype "passive"))
      (node (ref "IC4") (pin "4") (pinfunction "Y_4") (pintype "bidirectional"))
    )
    (net (code "38") (name "Net-(CAM_TRIGGERSD-S)") (class "Default")
      (node (ref "CAM_TRIGGERS") (pin "4") (pinfunction "S_4") (pintype "passive"))
      (node (ref "IC2") (pin "4") (pinfunction "Y_4") (pintype "bidirectional"))
    )
    (net (code "39") (name "Net-(D1-A)") (class "Default")
      (node (ref "D1") (pin "1") (pinfunction "A_1") (pintype "passive"))
      (node (ref "REWARD_VALVES") (pin "1") (pinfunction "S_1") (pintype "passive"))
      (node (ref "T2") (pin "3") (pinfunction "D_3") (pintype "passive"))
    )
    (net (code "40") (name "Net-(D4-A)") (class "Default")
      (node (ref "D4") (pin "1") (pinfunction "A_1") (pintype "passive"))
      (node (ref "REWARD_VALVES") (pin "3") (pinfunction "S_3") (pintype "passive"))
      (node (ref "T1") (pin "3") (pinfunction "D_3") (pintype "passive"))
    )
    (net (code "41") (name "Net-(IC1-3V3OUT)") (class "Default")
      (node (ref "C7") (pin "1") (pinfunction "1_1") (pintype "passive"))
      (node (ref "IC1") (pin "17") (pinfunction "3V3OUT_17") (pintype "output"))
    )
    (net (code "42") (name "Net-(IC1-~{RESET})") (class "Default")
      (node (ref "IC1") (pin "19") (pinfunction "~{RESET}_19") (pintype "input"))
      (node (ref "R18") (pin "2") (pinfunction "2_2") (pintype "passive"))
    )
    (net (code "43") (name "Net-(IC2-VCC)") (class "Default")
      (node (ref "C15") (pin "1") (pinfunction "1_1") (pintype "passive"))
      (node (ref "IC2") (pin "5") (pinfunction "VCC_5") (pintype "bidirectional"))
      (node (ref "R5") (pin "2") (pinfunction "2_2") (pintype "passive"))
      (node (ref "R6") (pin "2") (pinfunction "2_2") (pintype "passive"))
    )
    (net (code "44") (name "Net-(IC4-VCC)") (class "Default")
      (node (ref "C16") (pin "1") (pinfunction "1_1") (pintype "passive"))
      (node (ref "IC4") (pin "5") (pinfunction "VCC_5") (pintype "bidirectional"))
      (node (ref "R1") (pin "2") (pinfunction "2_2") (pintype "passive"))
      (node (ref "R2") (pin "2") (pinfunction "2_2") (pintype "passive"))
    )
    (net (code "45") (name "Net-(IC8-OC0B{slash}XCK0{slash}PD1)") (class "Default")
      (node (ref "IC8") (pin "21") (pinfunction "OC0B/XCK0/PD1_21") (pintype "bidirectional"))
      (node (ref "TP9") (pin "TP") (pinfunction "TP_TP") (pintype "input"))
    )
    (net (code "46") (name "Net-(IC8-PA4{slash}ADC4)") (class "Default")
      (node (ref "IC8") (pin "44") (pinfunction "PA4/ADC4_44") (pintype "bidirectional"))
      (node (ref "TP4") (pin "TP") (pinfunction "TP_TP") (pintype "input"))
    )
    (net (code "47") (name "Net-(IC8-PA5{slash}ADC5)") (class "Default")
      (node (ref "IC8") (pin "1") (pinfunction "PA5/ADC5_1") (pintype "bidirectional"))
      (node (ref "TP5") (pin "TP") (pinfunction "TP_TP") (pintype "input"))
    )
    (net (code "48") (name "Net-(IC8-PB2{slash}ADC10{slash}DAC0)") (class "Default")
      (node (ref "IC8") (pin "6") (pinfunction "PB2/ADC10/DAC0_6") (pintype "bidirectional"))
      (node (ref "TP6") (pin "TP") (pinfunction "TP_TP") (pintype "input"))
    )
    (net (code "49") (name "Net-(IC8-PC1{slash}OC0B{slash}XCK0{slash}SCL)") (class "Default")
      (node (ref "IC8") (pin "11") (pinfunction "PC1/OC0B/XCK0/SCL_11") (pintype "bidirectional"))
      (node (ref "TP8") (pin "TP") (pinfunction "TP_TP") (pintype "input"))
    )
    (net (code "50") (name "Net-(IC8-PR1{slash}XTAL1)") (class "Default")
      (node (ref "IC8") (pin "37") (pinfunction "PR1/XTAL1_37") (pintype "bidirectional"))
      (node (ref "OSC1") (pin "P$3") (pinfunction "OUTPUT_P$3") (pintype "passive"))
    )
    (net (code "51") (name "Net-(R10-Pad2)") (class "Default")
      (node (ref "R10") (pin "2") (pinfunction "2_2") (pintype "passive"))
      (node (ref "STATE") (pin "C") (pinfunction "C_C") (pintype "passive"))
    )
    (net (code "52") (name "Net-(X3-2)") (class "Default")
      (node (ref "IC7") (pin "P$4") (pinfunction "IO2_P$4") (pintype "bidirectional"))
      (node (ref "X3") (pin "P$2") (pinfunction "2_P$2") (pintype "bidirectional"))
    )
    (net (code "53") (name "Net-(X3-3)") (class "Default")
      (node (ref "IC7") (pin "P$6") (pinfunction "IO1_P$6") (pintype "bidirectional"))
      (node (ref "X3") (pin "P$3") (pinfunction "3_P$3") (pintype "bidirectional"))
    )
    (net (code "54") (name "Net-(X3-P$2)") (class "Default")
      (node (ref "R3") (pin "2") (pinfunction "2_2") (pintype "passive"))
      (node (ref "X3") (pin "SHIELD_2") (pinfunction "P$2_SHIELD_2") (pintype "bidirectional"))
    )
    (net (code "55") (name "Net-(X3-P$3)") (class "Default")
      (node (ref "C2") (pin "1") (pinfunction "1_1") (pintype "passive"))
      (node (ref "X3") (pin "SHIELD_3") (pinfunction "P$3_SHIELD_3") (pintype "bidirectional"))
    )
    (net (code "56") (name "unconnected-(IC1-CBUS0-Pad23)") (class "Default")
      (node (ref "IC1") (pin "23") (pinfunction "CBUS0_23") (pintype "bidirectional"))
    )
    (net (code "57") (name "unconnected-(IC1-CBUS1-Pad22)") (class "Default")
      (node (ref "IC1") (pin "22") (pinfunction "CBUS1_22") (pintype "bidirectional"))
    )
    (net (code "58") (name "unconnected-(IC1-CBUS2-Pad13)") (class "Default")
      (node (ref "IC1") (pin "13") (pinfunction "CBUS2_13") (pintype "bidirectional"))
    )
    (net (code "59") (name "unconnected-(IC1-CBUS3-Pad14)") (class "Default")
      (node (ref "IC1") (pin "14") (pinfunction "CBUS3_14") (pintype "bidirectional"))
    )
    (net (code "60") (name "unconnected-(IC1-CBUS4-Pad12)") (class "Default")
      (node (ref "IC1") (pin "12") (pinfunction "CBUS4_12") (pintype "bidirectional"))
    )
    (net (code "61") (name "unconnected-(IC1-OSCI-Pad27)") (class "Default")
      (node (ref "IC1") (pin "27") (pinfunction "OSCI_27") (pintype "input"))
    )
    (net (code "62") (name "unconnected-(IC1-OSCO-Pad28)") (class "Default")
      (node (ref "IC1") (pin "28") (pinfunction "OSCO_28") (pintype "output"))
    )
    (net (code "63") (name "unconnected-(IC1-~{DCD}-Pad10)") (class "Default")
      (node (ref "IC1") (pin "10") (pinfunction "~{DCD}_10") (pintype "input"))
    )
    (net (code "64") (name "unconnected-(IC1-~{DSR}-Pad9)") (class "Default")
      (node (ref "IC1") (pin "9") (pinfunction "~{DSR}_9") (pintype "input"))
    )
    (net (code "65") (name "unconnected-(IC1-~{DTR}-Pad2)") (class "Default")
      (node (ref "IC1") (pin "2") (pinfunction "~{DTR}_2") (pintype "output"))
    )
    (net (code "66") (name "unconnected-(IC1-~{RI}-Pad6)") (class "Default")
      (node (ref "IC1") (pin "6") (pinfunction "~{RI}_6") (pintype "input"))
    )
    (net (code "67") (name "unconnected-(IC2-NC-Pad1)") (class "Default")
      (node (ref "IC2") (pin "1") (pinfunction "NC_1") (pintype "no_connect"))
    )
    (net (code "68") (name "unconnected-(IC3-N{slash}C-Pad4)") (class "Default")
      (node (ref "IC3") (pin "4") (pinfunction "N/C_4") (pintype "bidirectional"))
    )
    (net (code "69") (name "unconnected-(IC4-NC-Pad1)") (class "Default")
      (node (ref "IC4") (pin "1") (pinfunction "NC_1") (pintype "no_connect"))
    )
    (net (code "70") (name "unconnected-(IC5-NC-Pad1)") (class "Default")
      (node (ref "IC5") (pin "1") (pinfunction "NC_1") (pintype "no_connect"))
    )
    (net (code "71") (name "unconnected-(IC6-NC-Pad1)") (class "Default")
      (node (ref "IC6") (pin "1") (pinfunction "NC_1") (pintype "no_connect"))
    )
    (net (code "72") (name "unconnected-(IC8-PA2{slash}ADC2-Pad42)") (class "Default")
      (node (ref "IC8") (pin "42") (pinfunction "PA2/ADC2_42") (pintype "bidirectional"))
    )
    (net (code "73") (name "unconnected-(IC8-PA3{slash}ADC3-Pad43)") (class "Default")
      (node (ref "IC8") (pin "43") (pinfunction "PA3/ADC3_43") (pintype "bidirectional"))
    )
    (net (code "74") (name "unconnected-(IC8-PB3{slash}ADC11{slash}DAC1-Pad7)") (class "Default")
      (node (ref "IC8") (pin "7") (pinfunction "PB3/ADC11/DAC1_7") (pintype "bidirectional"))
    )
    (net (code "75") (name "unconnected-(IC8-PC3{slash}OC0D{slash}TXD0-Pad13)") (class "Default")
      (node (ref "IC8") (pin "13") (pinfunction "PC3/OC0D/TXD0_13") (pintype "bidirectional"))
    )
    (net (code "76") (name "unconnected-(OSC1-STANDBY#-PadP$1)") (class "Default")
      (node (ref "OSC1") (pin "P$1") (pinfunction "STANDBY#_P$1") (pintype "passive"))
    )
    (net (code "77") (name "unconnected-(SV2-Pad3)") (class "Default")
      (node (ref "SV2") (pin "3") (pinfunction "3_3") (pintype "passive"))
    )
    (net (code "78") (name "unconnected-(SV2-Pad4)") (class "Default")
      (node (ref "SV2") (pin "4") (pinfunction "4_4") (pintype "passive"))
    )
    (net (code "79") (name "unconnected-(X1I-1-Pad8)") (class "Default")
      (node (ref "X1") (pin "8") (pinfunction "1_8") (pintype "passive"))
    )
    (net (code "80") (name "unconnected-(X1J-1-Pad9)") (class "Default")
      (node (ref "X1") (pin "9") (pinfunction "1_9") (pintype "passive"))
    )
    (net (code "81") (name "unconnected-(X2I-1-Pad8)") (class "Default")
      (node (ref "X2") (pin "8") (pinfunction "1_8") (pintype "passive"))
    )
    (net (code "82") (name "unconnected-(X2J-1-Pad9)") (class "Default")
      (node (ref "X2") (pin "9") (pinfunction "1_9") (pintype "passive"))
    )
    (net (code "83") (name "unconnected-(X3-4-PadP$4)") (class "Default")
      (node (ref "X3") (pin "P$4") (pinfunction "4_P$4") (pintype "bidirectional"))
    )
    (net (code "84") (name "unconnected-(X3-P$1-PadSHIELD_1)") (class "Default")
      (node (ref "X3") (pin "SHIELD_1") (pinfunction "P$1_SHIELD_1") (pintype "bidirectional"))
    )
    (net (code "85") (name "unconnected-(X3-P$4-PadSHIELD_4)") (class "Default")
      (node (ref "X3") (pin "SHIELD_4") (pinfunction "P$4_SHIELD_4") (pintype "bidirectional"))
    )
  )
)
